# Relay_IO.net
KiCad netlist of a schematic drawn in Altium Designer
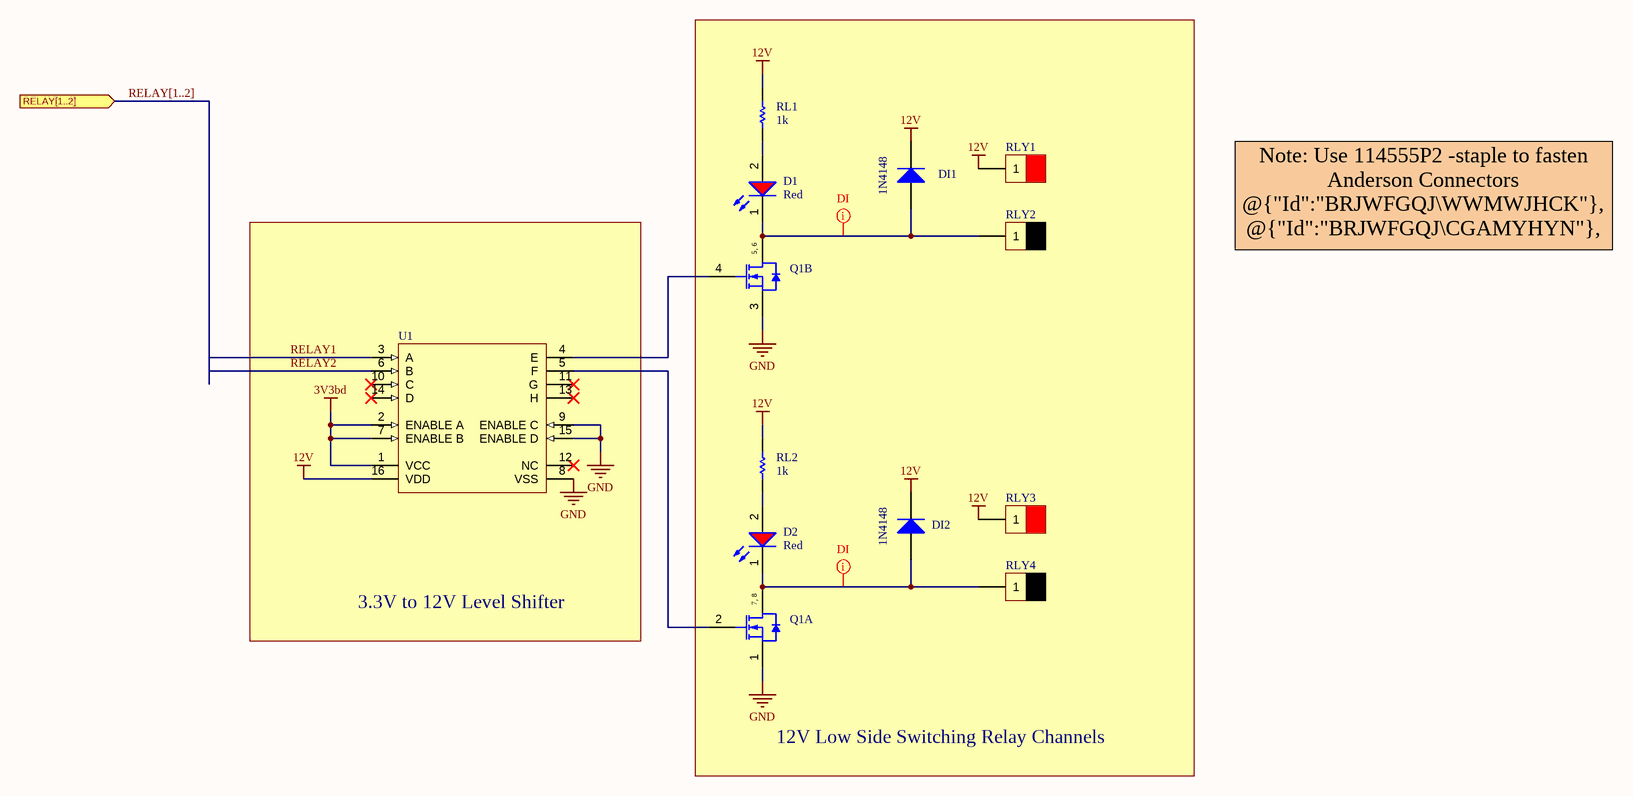
[diagram p0:  Relay_IO.SchDoc]

(export (version "E")
  (design (tool "Eeschema 10.0.6"))
  (components
    (comp (ref "D1")
      (value "LED_Red0603")
      (footprint "0603_A")
      (description "Single Color LED, Red, Water Clear, 1.1mm")
      (fields (field (name "COLOR") "Red"))
      (libsource (lib "Advanced] Training Course - A365") (part "LED_Red_2A-1K"))
    )
    (comp (ref "D2")
      (value "LED_Red0603")
      (footprint "0603_A")
      (description "Single Color LED, Red, Water Clear, 1.1mm")
      (fields (field (name "COLOR") "Red"))
      (libsource (lib "Advanced] Training Course - A365") (part "LED_Red_2A-1K"))
    )
    (comp (ref "DI1")
      (value "1N4148")
      (footprint "DO-41")
      (description "Rectifier Diode, 1 Phase, 1 Element, 1A, 100V V(RRM), Silicon, DO-41")
      (libsource (lib "Advanced] Training Course - A365") (part "Diode  General"))
    )
    (comp (ref "DI2")
      (value "1N4148")
      (footprint "DO-41")
      (description "Rectifier Diode, 1 Phase, 1 Element, 1A, 100V V(RRM), Silicon, DO-41")
      (libsource (lib "Advanced] Training Course - A365") (part "Diode  General"))
    )
    (comp (ref "Q1")
      (value "NTHD4508NT1")
      (footprint "ONSC-CHIPFET-8-1206A-03_S2_V")
      (description "Small Signal Field-Effect Transistor")
      (libsource (lib "Advanced] Training Course - A365") (part "MOSFET Dual N-Channel"))
    )
    (comp (ref "RL1")
      (value "Res1K_0805")
      (footprint "0805_L")
      (fields
        (field (name "MANUFACTURER") "Panasonic Electronic Components")
        (field (name "MANUFACTURER PART NUMBER") "ERJ-6GEYJ102V")
        (field (name "RESISTANCE (OHMS)") "1k")
        (field (name "TOLERANCE") "5%")
        (field (name "SOURCE") "WCT.SchLib")
      )
      (libsource (lib "Advanced] Training Course - A365") (part "Resistor General"))
    )
    (comp (ref "RL2")
      (value "Res1K_0805")
      (footprint "0805_L")
      (fields
        (field (name "MANUFACTURER") "Panasonic Electronic Components")
        (field (name "MANUFACTURER PART NUMBER") "ERJ-6GEYJ102V")
        (field (name "RESISTANCE (OHMS)") "1k")
        (field (name "TOLERANCE") "5%")
        (field (name "SOURCE") "WCT.SchLib")
      )
      (libsource (lib "Advanced] Training Course - A365") (part "Resistor General"))
    )
    (comp (ref "RLY1")
      (value "Anderson-1Pin RED_PCB_RHT")
      (footprint "Anderson_RED_RHT_BOT")
      (description "Connector Accessory, Contact, Copper Alloy")
      (libsource (lib "TC - Altium Essentials Course A365 13") (part "Anderson-1Pin RED_PCB_RHT"))
    )
    (comp (ref "RLY2")
      (value "Anderson-1Pin BLK_PCB_RHT")
      (footprint "Anderson_BLK_RHT_BOT")
      (description "Connector Accessory, Contact, Copper Alloy")
      (libsource (lib "Advanced] Training Course - A365") (part "Anderson-1Pin BLK_PCB_RHT"))
    )
    (comp (ref "RLY3")
      (value "Anderson-1Pin RED_PCB_RHT")
      (footprint "Anderson_RED_RHT_BOT")
      (description "Connector Accessory, Contact, Copper Alloy")
      (libsource (lib "TC - Altium Essentials Course A365 13") (part "Anderson-1Pin RED_PCB_RHT"))
    )
    (comp (ref "RLY4")
      (value "Anderson-1Pin BLK_PCB_RHT")
      (footprint "Anderson_BLK_RHT_BOT")
      (description "Connector Accessory, Contact, Copper Alloy")
      (libsource (lib "Advanced] Training Course - A365") (part "Anderson-1Pin BLK_PCB_RHT"))
    )
    (comp (ref "U1")
      (value "CD40109BPW")
      (footprint "PW0016A_M")
      (fields
        (field (name "MANUFACTURER") "Texas Instruments")
        (field (name "MANUFACTURER PART NUMBER") "CD40109BPWR")
        (field (name "AVAILABLE PREVIEW IMAGES") "2D")
        (field (name "SOURCE") "WCT.SchLib")
      )
      (libsource (lib "Advanced] Training Course - A365") (part "CD40109BPW"))
    )
  )
  (nets
    (net (code "1") (name "/RELAY1") (class "Default")
      (node (ref "U1") (pin "3") (pinfunction "A_3") (pintype "input"))
    )
    (net (code "2") (name "/RELAY2") (class "Default")
      (node (ref "U1") (pin "6") (pinfunction "B_6") (pintype "input"))
    )
    (net (code "4") (name "3V3bd") (class "Default")
      (node (ref "U1") (pin "1") (pinfunction "VCC_1") (pintype "power_in"))
      (node (ref "U1") (pin "2") (pinfunction "ENABLE_A_2") (pintype "input"))
      (node (ref "U1") (pin "7") (pinfunction "ENABLE_B_7") (pintype "input"))
    )
    (net (code "5") (name "12V") (class "Default")
      (node (ref "DI1") (pin "2") (pinfunction "K_2") (pintype "passive"))
      (node (ref "DI2") (pin "2") (pinfunction "K_2") (pintype "passive"))
      (node (ref "RL1") (pin "2") (pinfunction "2_2") (pintype "passive"))
      (node (ref "RL2") (pin "2") (pinfunction "2_2") (pintype "passive"))
      (node (ref "RLY1") (pin "1") (pinfunction "1_1") (pintype "passive"))
      (node (ref "RLY3") (pin "1") (pinfunction "1_1") (pintype "passive"))
      (node (ref "U1") (pin "16") (pinfunction "VDD_16") (pintype "power_in"))
    )
    (net (code "6") (name "GND") (class "Default")
      (node (ref "Q1") (pin "1") (pinfunction "S1_1") (pintype "passive"))
      (node (ref "Q1") (pin "3") (pinfunction "S2_3") (pintype "passive"))
      (node (ref "U1") (pin "15") (pinfunction "ENABLE_D_15") (pintype "input"))
      (node (ref "U1") (pin "8") (pinfunction "VSS_8") (pintype "power_in"))
      (node (ref "U1") (pin "9") (pinfunction "ENABLE_C_9") (pintype "input"))
    )
    (net (code "7") (name "Net-(D1-A)") (class "Default")
      (node (ref "D1") (pin "2") (pinfunction "A_2") (pintype "passive"))
      (node (ref "RL1") (pin "1") (pinfunction "1_1") (pintype "passive"))
    )
    (net (code "8") (name "Net-(D1-K)") (class "Default")
      (node (ref "D1") (pin "1") (pinfunction "K_1") (pintype "passive"))
      (node (ref "DI1") (pin "1") (pinfunction "A_1") (pintype "passive"))
      (node (ref "Q1") (pin "5") (pinfunction "D2_5") (pintype "passive"))
      (node (ref "Q1") (pin "6") (pinfunction "D2_6") (pintype "passive"))
      (node (ref "RLY2") (pin "1") (pinfunction "1_1") (pintype "passive"))
    )
    (net (code "9") (name "Net-(D2-A)") (class "Default")
      (node (ref "D2") (pin "2") (pinfunction "A_2") (pintype "passive"))
      (node (ref "RL2") (pin "1") (pinfunction "1_1") (pintype "passive"))
    )
    (net (code "10") (name "Net-(D2-K)") (class "Default")
      (node (ref "D2") (pin "1") (pinfunction "K_1") (pintype "passive"))
      (node (ref "DI2") (pin "1") (pinfunction "A_1") (pintype "passive"))
      (node (ref "Q1") (pin "7") (pinfunction "D1_7") (pintype "passive"))
      (node (ref "Q1") (pin "8") (pinfunction "D1_8") (pintype "passive"))
      (node (ref "RLY4") (pin "1") (pinfunction "1_1") (pintype "passive"))
    )
    (net (code "11") (name "Net-(Q1A-G1)") (class "Default")
      (node (ref "Q1") (pin "2") (pinfunction "G1_2") (pintype "passive"))
      (node (ref "U1") (pin "5") (pinfunction "F_5") (pintype "tri_state"))
    )
    (net (code "12") (name "Net-(Q1B-G2)") (class "Default")
      (node (ref "Q1") (pin "4") (pinfunction "G2_4") (pintype "passive"))
      (node (ref "U1") (pin "4") (pinfunction "E_4") (pintype "tri_state"))
    )
    (net (code "13") (name "unconnected-(U1-C-Pad10)") (class "Default")
      (node (ref "U1") (pin "10") (pinfunction "C_10") (pintype "input+no_connect"))
    )
    (net (code "14") (name "unconnected-(U1-D-Pad14)") (class "Default")
      (node (ref "U1") (pin "14") (pinfunction "D_14") (pintype "input+no_connect"))
    )
    (net (code "15") (name "unconnected-(U1-G-Pad11)") (class "Default")
      (node (ref "U1") (pin "11") (pinfunction "G_11") (pintype "tri_state+no_connect"))
    )
    (net (code "16") (name "unconnected-(U1-H-Pad13)") (class "Default")
      (node (ref "U1") (pin "13") (pinfunction "H_13") (pintype "tri_state+no_connect"))
    )
    (net (code "17") (name "unconnected-(U1-NC-Pad12)") (class "Default")
      (node (ref "U1") (pin "12") (pinfunction "NC_12") (pintype "passive+no_connect"))
    )
  )
)
